# fpga.net
KiCad netlist of a schematic drawn in Altium Designer
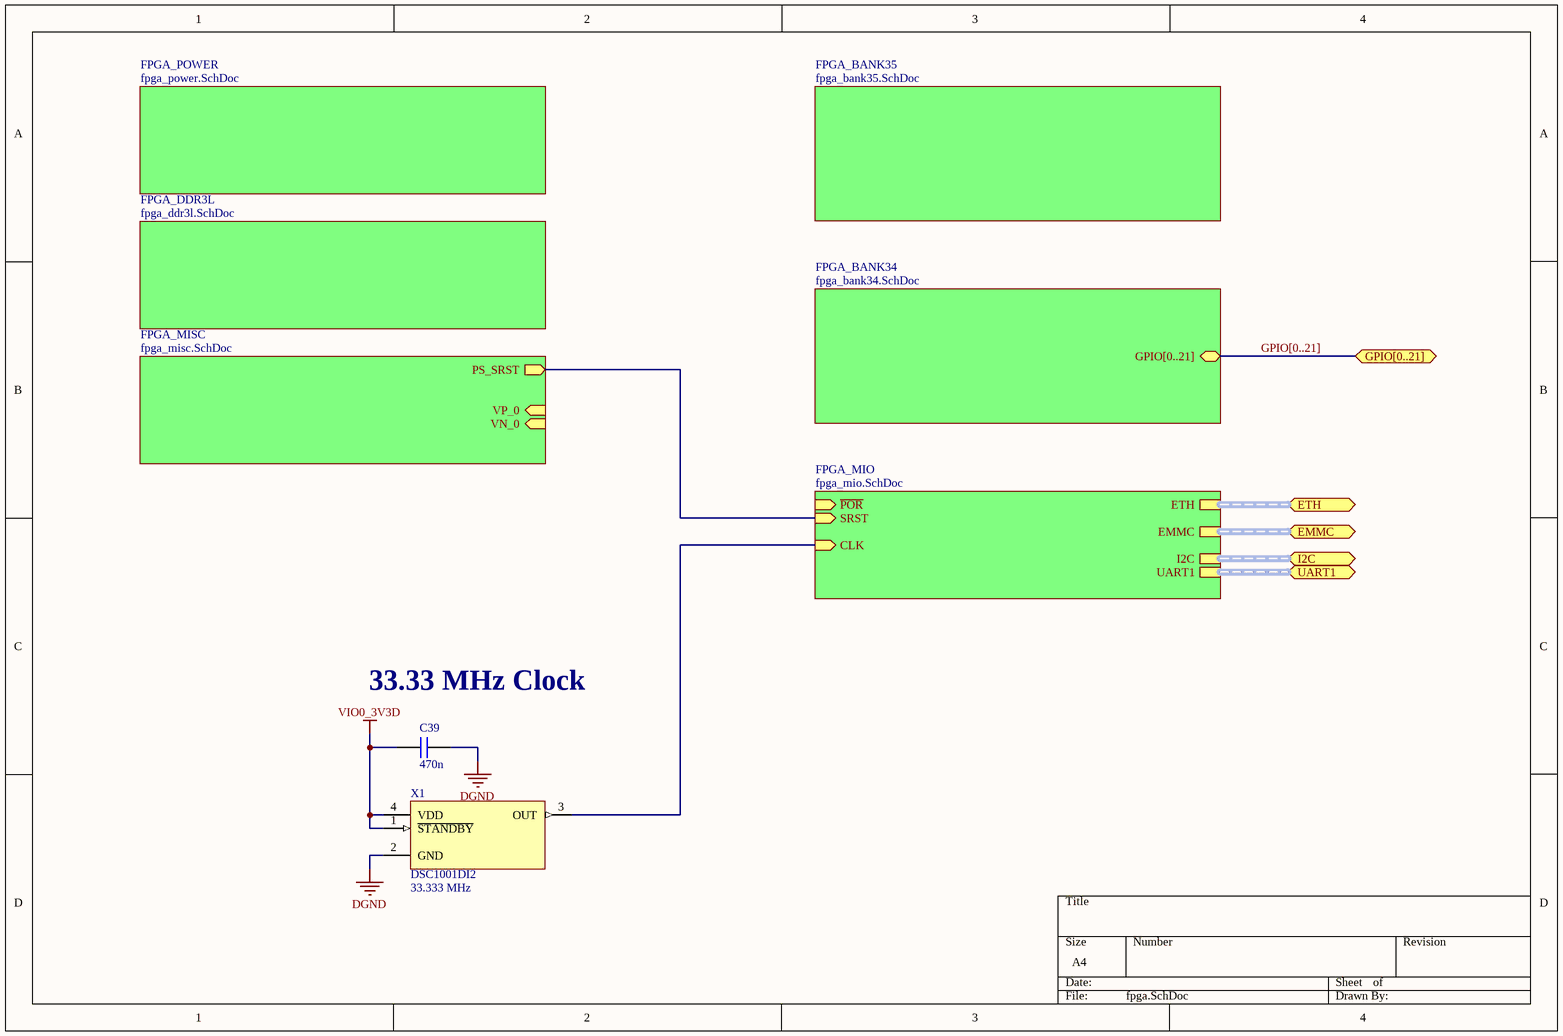
[diagram p0: fpga.SchDoc]

(export (version "E")
  (design (tool "Eeschema 10.0.6"))
  (components
    (comp (ref "C39")
      (value "470n")
      (footprint "CAPC1608X08N")
      (description "Capacitor")
      (fields (field (name "Comment") "cap"))
      (libsource (lib "lib_passives") (part "cap"))
    )
    (comp (ref "X1")
      (value "DSC1001DI2")
      (footprint "DFN165P200X90-4N_DSC1001DIx")
      (description "1.8V-3.3V Low-Power Precision CMOS Oscillators")
      (fields (field (name "FREQUENCY") "33.333 MHz"))
      (libsource (lib "lib_microchip") (part "dsc1001dix"))
    )
  )
  (nets
    (net (code "23") (name "/CLK") (class "Default")
      (node (ref "X1") (pin "3") (pinfunction "OUT_3") (pintype "output"))
    )
    (net (code "37") (name "DGND") (class "Default")
      (node (ref "C39") (pin "1") (pinfunction "1_1") (pintype "passive"))
      (node (ref "X1") (pin "2") (pinfunction "GND_2") (pintype "power_in"))
    )
    (net (code "38") (name "VIO0_3V3D") (class "Default")
      (node (ref "C39") (pin "2") (pinfunction "2_2") (pintype "passive"))
      (node (ref "X1") (pin "1") (pinfunction "STANDBY_1") (pintype "input"))
      (node (ref "X1") (pin "4") (pinfunction "VDD_4") (pintype "power_in"))
    )
  )
)
